# L293D_Module.net
KiCad netlist of a schematic drawn in EAGLE
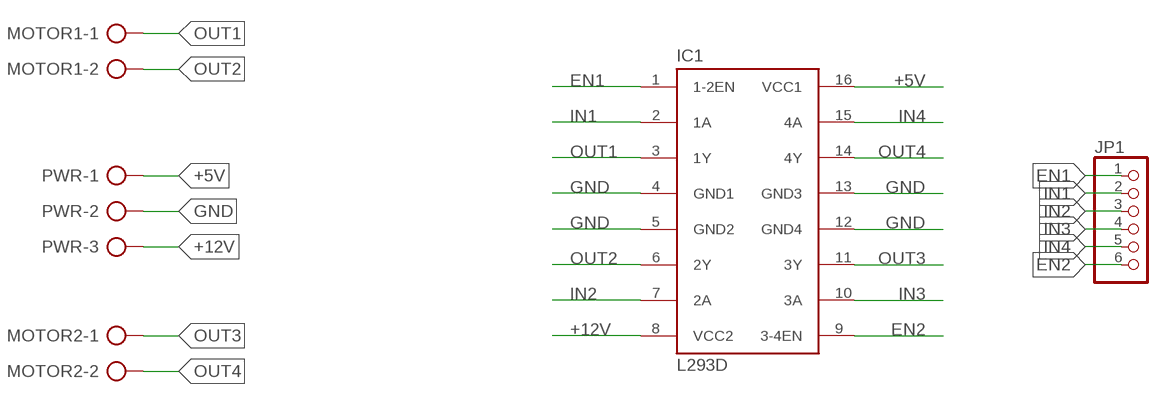
[diagram p0: schematic, sheet 1]

(export (version "E")
  (design (tool "Eeschema 10.0.6"))
  (components
    (comp (ref "IC1")
      (value "L293D")
      (footprint "eagle-import:DIL16")
      (libsource (lib "eagle-import") (part "L293D"))
    )
    (comp (ref "JP1")
      (value "PINHD-1X6")
      (footprint "eagle-import:1X06")
      (libsource (lib "eagle-import") (part "PINHD-1X6"))
    )
    (comp (ref "MOTOR1")
      (value "AK500/2-H")
      (footprint "eagle-import:AK500_2-H")
      (libsource (lib "eagle-import") (part "AK500/2-H"))
    )
    (comp (ref "MOTOR2")
      (value "AK500/2-H")
      (footprint "eagle-import:AK500_2-H")
      (libsource (lib "eagle-import") (part "AK500/2-H"))
    )
    (comp (ref "PWR")
      (value "AK500/3-H")
      (footprint "eagle-import:AK500_3-H")
      (libsource (lib "eagle-import") (part "AK500/3-H"))
    )
  )
  (nets
    (net (code "1") (name "+5V") (class "Default")
      (node (ref "IC1") (pin "16") (pinfunction "VCC1_16") (pintype "power_in"))
      (node (ref "PWR") (pin "1") (pinfunction "KL_1") (pintype "passive"))
    )
    (net (code "2") (name "+12V") (class "Default")
      (node (ref "IC1") (pin "8") (pinfunction "VCC2_8") (pintype "power_in"))
      (node (ref "PWR") (pin "3") (pinfunction "KL_3") (pintype "passive"))
    )
    (net (code "3") (name "EN1") (class "Default")
      (node (ref "IC1") (pin "1") (pinfunction "1-2EN_1") (pintype "input"))
      (node (ref "JP1") (pin "1") (pinfunction "1_1") (pintype "passive"))
    )
    (net (code "4") (name "EN2") (class "Default")
      (node (ref "IC1") (pin "9") (pinfunction "3-4EN_9") (pintype "input"))
      (node (ref "JP1") (pin "6") (pinfunction "6_6") (pintype "passive"))
    )
    (net (code "5") (name "GND") (class "Default")
      (node (ref "IC1") (pin "12") (pinfunction "GND4_12") (pintype "power_in"))
      (node (ref "IC1") (pin "13") (pinfunction "GND3_13") (pintype "power_in"))
      (node (ref "IC1") (pin "4") (pinfunction "GND1_4") (pintype "power_in"))
      (node (ref "IC1") (pin "5") (pinfunction "GND2_5") (pintype "power_in"))
      (node (ref "PWR") (pin "2") (pinfunction "KL_2") (pintype "passive"))
    )
    (net (code "6") (name "IN1") (class "Default")
      (node (ref "IC1") (pin "2") (pinfunction "1A_2") (pintype "input"))
      (node (ref "JP1") (pin "2") (pinfunction "2_2") (pintype "passive"))
    )
    (net (code "7") (name "IN2") (class "Default")
      (node (ref "IC1") (pin "7") (pinfunction "2A_7") (pintype "input"))
      (node (ref "JP1") (pin "3") (pinfunction "3_3") (pintype "passive"))
    )
    (net (code "8") (name "IN3") (class "Default")
      (node (ref "IC1") (pin "10") (pinfunction "3A_10") (pintype "input"))
      (node (ref "JP1") (pin "4") (pinfunction "4_4") (pintype "passive"))
    )
    (net (code "9") (name "IN4") (class "Default")
      (node (ref "IC1") (pin "15") (pinfunction "4A_15") (pintype "input"))
      (node (ref "JP1") (pin "5") (pinfunction "5_5") (pintype "passive"))
    )
    (net (code "10") (name "OUT1") (class "Default")
      (node (ref "IC1") (pin "3") (pinfunction "1Y_3") (pintype "output"))
      (node (ref "MOTOR1") (pin "1") (pinfunction "KL_1") (pintype "passive"))
    )
    (net (code "11") (name "OUT2") (class "Default")
      (node (ref "IC1") (pin "6") (pinfunction "2Y_6") (pintype "output"))
      (node (ref "MOTOR1") (pin "2") (pinfunction "KL_2") (pintype "passive"))
    )
    (net (code "12") (name "OUT3") (class "Default")
      (node (ref "IC1") (pin "11") (pinfunction "3Y_11") (pintype "output"))
      (node (ref "MOTOR2") (pin "1") (pinfunction "KL_1") (pintype "passive"))
    )
    (net (code "13") (name "OUT4") (class "Default")
      (node (ref "IC1") (pin "14") (pinfunction "4Y_14") (pintype "output"))
      (node (ref "MOTOR2") (pin "2") (pinfunction "KL_2") (pintype "passive"))
    )
  )
)
